# identity-disk-clock.net
KiCad netlist of a schematic drawn in EAGLE
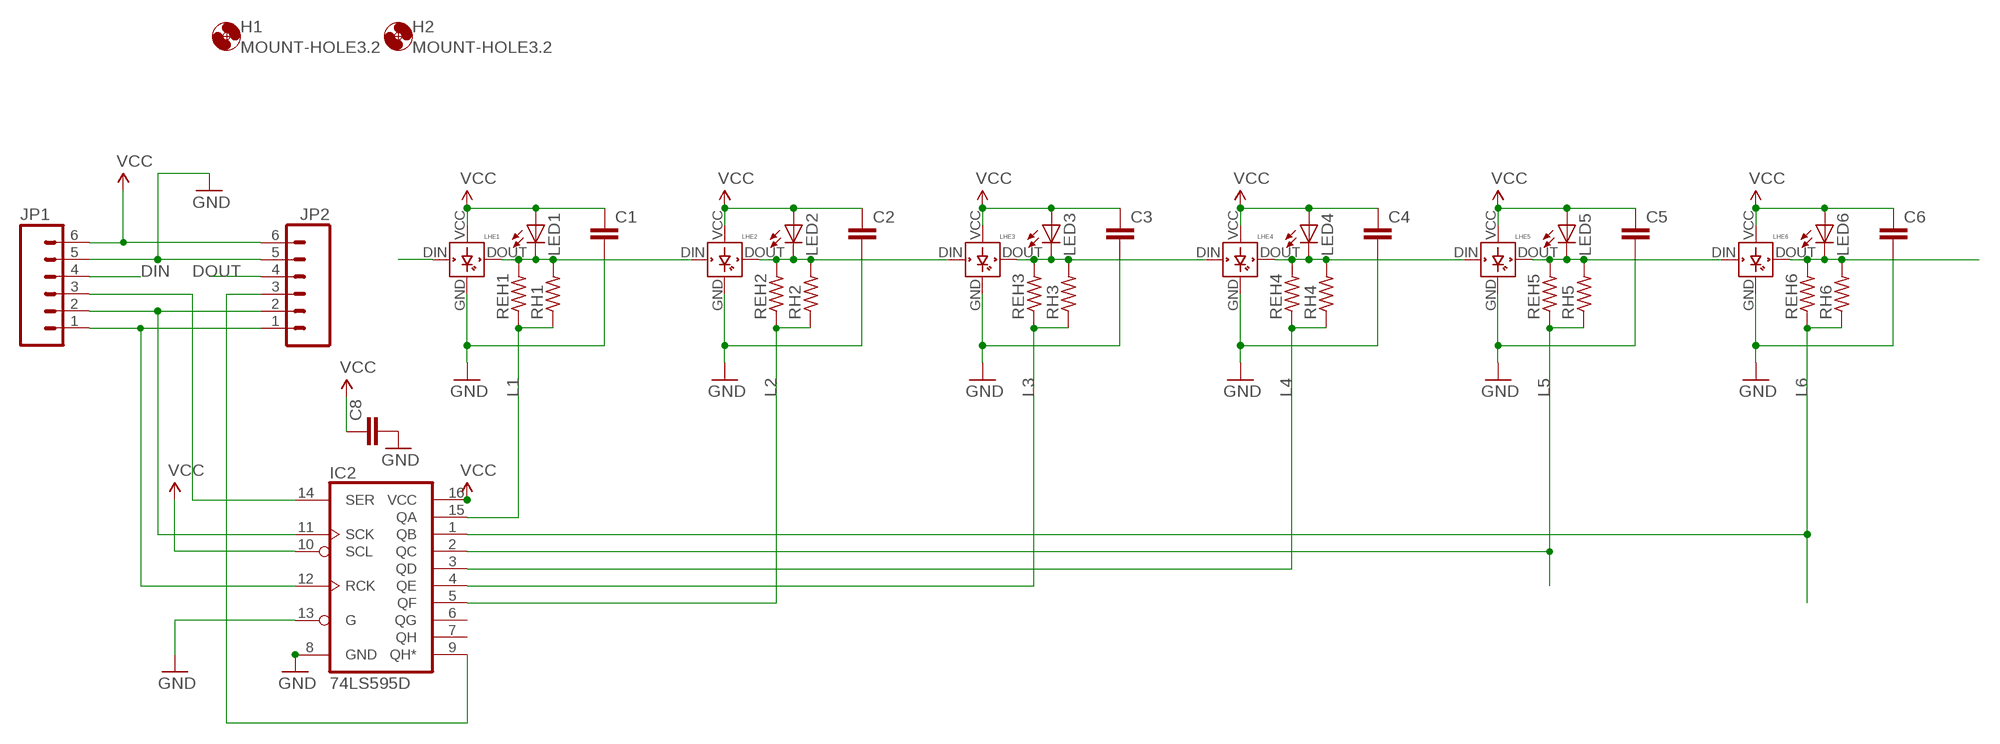
[diagram p0: schematic, sheet 1]

(export (version "E")
  (design (tool "Eeschema 10.0.6"))
  (components
    (comp (ref "C1")
      (value "C-EU050-024X044")
      (footprint "eagle-import:C050-024X044")
      (libsource (lib "eagle-import") (part "C-EU050-024X044"))
    )
    (comp (ref "C2")
      (value "C-EU050-024X044")
      (footprint "eagle-import:C050-024X044")
      (libsource (lib "eagle-import") (part "C-EU050-024X044"))
    )
    (comp (ref "C3")
      (value "C-EU050-024X044")
      (footprint "eagle-import:C050-024X044")
      (libsource (lib "eagle-import") (part "C-EU050-024X044"))
    )
    (comp (ref "C4")
      (value "C-EU050-024X044")
      (footprint "eagle-import:C050-024X044")
      (libsource (lib "eagle-import") (part "C-EU050-024X044"))
    )
    (comp (ref "C5")
      (value "C-EU050-024X044")
      (footprint "eagle-import:C050-024X044")
      (libsource (lib "eagle-import") (part "C-EU050-024X044"))
    )
    (comp (ref "C6")
      (value "C-EU050-024X044")
      (footprint "eagle-import:C050-024X044")
      (libsource (lib "eagle-import") (part "C-EU050-024X044"))
    )
    (comp (ref "C8")
      (value "C-EUC0402")
      (footprint "eagle-import:C0402")
      (libsource (lib "eagle-import") (part "resistor_C-EUC0402"))
    )
    (comp (ref "H1")
      (value "MOUNT-HOLE3.2")
      (footprint "eagle-import:3,2")
      (libsource (lib "eagle-import") (part "MOUNT-HOLE3.2"))
    )
    (comp (ref "H2")
      (value "MOUNT-HOLE3.2")
      (footprint "eagle-import:3,2")
      (libsource (lib "eagle-import") (part "MOUNT-HOLE3.2"))
    )
    (comp (ref "IC2")
      (value "74LS595D")
      (footprint "eagle-import:SO16")
      (libsource (lib "eagle-import") (part "74595DLS"))
    )
    (comp (ref "JP1")
      (value "M06LOCK")
      (footprint "eagle-import:1X06_LOCK")
      (libsource (lib "eagle-import") (part "M06LOCK"))
    )
    (comp (ref "JP2")
      (value "M06LOCK")
      (footprint "eagle-import:1X06_LOCK")
      (libsource (lib "eagle-import") (part "M06LOCK"))
    )
    (comp (ref "LED1")
      (value "LEDMICRO-SIDELED")
      (footprint "eagle-import:MICRO-SIDELED")
      (libsource (lib "eagle-import") (part "LEDMICRO-SIDELED"))
    )
    (comp (ref "LED2")
      (value "LEDMICRO-SIDELED")
      (footprint "eagle-import:MICRO-SIDELED")
      (libsource (lib "eagle-import") (part "LEDMICRO-SIDELED"))
    )
    (comp (ref "LED3")
      (value "LEDMICRO-SIDELED")
      (footprint "eagle-import:MICRO-SIDELED")
      (libsource (lib "eagle-import") (part "LEDMICRO-SIDELED"))
    )
    (comp (ref "LED4")
      (value "LEDMICRO-SIDELED")
      (footprint "eagle-import:MICRO-SIDELED")
      (libsource (lib "eagle-import") (part "LEDMICRO-SIDELED"))
    )
    (comp (ref "LED5")
      (value "LEDMICRO-SIDELED")
      (footprint "eagle-import:MICRO-SIDELED")
      (libsource (lib "eagle-import") (part "LEDMICRO-SIDELED"))
    )
    (comp (ref "LED6")
      (value "LEDMICRO-SIDELED")
      (footprint "eagle-import:MICRO-SIDELED")
      (libsource (lib "eagle-import") (part "LEDMICRO-SIDELED"))
    )
    (comp (ref "LHE1")
      (value "WS2812B")
      (footprint "eagle-import:LED5MMRGBNP")
      (libsource (lib "eagle-import") (part "WS2812B"))
    )
    (comp (ref "LHE2")
      (value "WS2812B")
      (footprint "eagle-import:LED5MMRGBNP")
      (libsource (lib "eagle-import") (part "WS2812B"))
    )
    (comp (ref "LHE3")
      (value "WS2812B")
      (footprint "eagle-import:LED5MMRGBNP")
      (libsource (lib "eagle-import") (part "WS2812B"))
    )
    (comp (ref "LHE4")
      (value "WS2812B")
      (footprint "eagle-import:LED5MMRGBNP")
      (libsource (lib "eagle-import") (part "WS2812B"))
    )
    (comp (ref "LHE5")
      (value "WS2812B")
      (footprint "eagle-import:LED5MMRGBNP")
      (libsource (lib "eagle-import") (part "WS2812B"))
    )
    (comp (ref "LHE6")
      (value "WS2812B")
      (footprint "eagle-import:LED5MMRGBNP")
      (libsource (lib "eagle-import") (part "WS2812B"))
    )
    (comp (ref "REH1")
      (value "R-US_R0402")
      (footprint "eagle-import:R0402")
      (libsource (lib "eagle-import") (part "R-US_R0402"))
    )
    (comp (ref "REH2")
      (value "R-US_R0402")
      (footprint "eagle-import:R0402")
      (libsource (lib "eagle-import") (part "R-US_R0402"))
    )
    (comp (ref "REH3")
      (value "R-US_R0402")
      (footprint "eagle-import:R0402")
      (libsource (lib "eagle-import") (part "R-US_R0402"))
    )
    (comp (ref "REH4")
      (value "R-US_R0402")
      (footprint "eagle-import:R0402")
      (libsource (lib "eagle-import") (part "R-US_R0402"))
    )
    (comp (ref "REH5")
      (value "R-US_R0402")
      (footprint "eagle-import:R0402")
      (libsource (lib "eagle-import") (part "R-US_R0402"))
    )
    (comp (ref "REH6")
      (value "R-US_R0402")
      (footprint "eagle-import:R0402")
      (libsource (lib "eagle-import") (part "R-US_R0402"))
    )
    (comp (ref "RH1")
      (value "R-US_0204/5")
      (footprint "eagle-import:0204_5")
      (libsource (lib "eagle-import") (part "R-US_0204/5"))
    )
    (comp (ref "RH2")
      (value "R-US_0204/5")
      (footprint "eagle-import:0204_5")
      (libsource (lib "eagle-import") (part "R-US_0204/5"))
    )
    (comp (ref "RH3")
      (value "R-US_0204/5")
      (footprint "eagle-import:0204_5")
      (libsource (lib "eagle-import") (part "R-US_0204/5"))
    )
    (comp (ref "RH4")
      (value "R-US_0204/5")
      (footprint "eagle-import:0204_5")
      (libsource (lib "eagle-import") (part "R-US_0204/5"))
    )
    (comp (ref "RH5")
      (value "R-US_0204/5")
      (footprint "eagle-import:0204_5")
      (libsource (lib "eagle-import") (part "R-US_0204/5"))
    )
    (comp (ref "RH6")
      (value "R-US_0204/5")
      (footprint "eagle-import:0204_5")
      (libsource (lib "eagle-import") (part "R-US_0204/5"))
    )
  )
  (nets
    (net (code "1") (name "/DIN") (class "Default")
      (node (ref "JP1") (pin "4") (pinfunction "4_4") (pintype "passive"))
      (node (ref "LHE1") (pin "DIN") (pinfunction "DIN_DIN") (pintype "input"))
    )
    (net (code "2") (name "/DOUT") (class "Default")
      (node (ref "JP2") (pin "4") (pinfunction "4_4") (pintype "passive"))
      (node (ref "LED6") (pin "C") (pinfunction "C_C") (pintype "passive"))
      (node (ref "LHE6") (pin "DOUT") (pinfunction "DOUT_DOUT") (pintype "output"))
      (node (ref "REH6") (pin "2") (pinfunction "2_2") (pintype "passive"))
      (node (ref "RH6") (pin "2") (pinfunction "2_2") (pintype "passive"))
    )
    (net (code "3") (name "/L1") (class "Default")
      (node (ref "IC2") (pin "15") (pinfunction "QA_15") (pintype "tri_state"))
      (node (ref "REH1") (pin "1") (pinfunction "1_1") (pintype "passive"))
      (node (ref "RH1") (pin "1") (pinfunction "1_1") (pintype "passive"))
    )
    (net (code "4") (name "/L2") (class "Default")
      (node (ref "IC2") (pin "5") (pinfunction "QF_5") (pintype "tri_state"))
      (node (ref "REH2") (pin "1") (pinfunction "1_1") (pintype "passive"))
      (node (ref "RH2") (pin "1") (pinfunction "1_1") (pintype "passive"))
    )
    (net (code "5") (name "/L3") (class "Default")
      (node (ref "IC2") (pin "4") (pinfunction "QE_4") (pintype "tri_state"))
      (node (ref "REH3") (pin "1") (pinfunction "1_1") (pintype "passive"))
      (node (ref "RH3") (pin "1") (pinfunction "1_1") (pintype "passive"))
    )
    (net (code "6") (name "/L4") (class "Default")
      (node (ref "IC2") (pin "3") (pinfunction "QD_3") (pintype "tri_state"))
      (node (ref "REH4") (pin "1") (pinfunction "1_1") (pintype "passive"))
      (node (ref "RH4") (pin "1") (pinfunction "1_1") (pintype "passive"))
    )
    (net (code "7") (name "/L5") (class "Default")
      (node (ref "IC2") (pin "2") (pinfunction "QC_2") (pintype "tri_state"))
      (node (ref "REH5") (pin "1") (pinfunction "1_1") (pintype "passive"))
      (node (ref "RH5") (pin "1") (pinfunction "1_1") (pintype "passive"))
    )
    (net (code "8") (name "/L6") (class "Default")
      (node (ref "IC2") (pin "1") (pinfunction "QB_1") (pintype "tri_state"))
      (node (ref "REH6") (pin "1") (pinfunction "1_1") (pintype "passive"))
      (node (ref "RH6") (pin "1") (pinfunction "1_1") (pintype "passive"))
    )
    (net (code "9") (name "GND") (class "Default")
      (node (ref "C1") (pin "2") (pinfunction "2_2") (pintype "passive"))
      (node (ref "C2") (pin "2") (pinfunction "2_2") (pintype "passive"))
      (node (ref "C3") (pin "2") (pinfunction "2_2") (pintype "passive"))
      (node (ref "C4") (pin "2") (pinfunction "2_2") (pintype "passive"))
      (node (ref "C5") (pin "2") (pinfunction "2_2") (pintype "passive"))
      (node (ref "C6") (pin "2") (pinfunction "2_2") (pintype "passive"))
      (node (ref "C8") (pin "2") (pinfunction "2_2") (pintype "passive"))
      (node (ref "IC2") (pin "13") (pinfunction "G_13") (pintype "input"))
      (node (ref "IC2") (pin "8") (pinfunction "GND_8") (pintype "power_in"))
      (node (ref "JP1") (pin "5") (pinfunction "5_5") (pintype "passive"))
      (node (ref "JP2") (pin "5") (pinfunction "5_5") (pintype "passive"))
      (node (ref "LHE1") (pin "GND") (pinfunction "GND_GND") (pintype "bidirectional"))
      (node (ref "LHE2") (pin "GND") (pinfunction "GND_GND") (pintype "bidirectional"))
      (node (ref "LHE3") (pin "GND") (pinfunction "GND_GND") (pintype "bidirectional"))
      (node (ref "LHE4") (pin "GND") (pinfunction "GND_GND") (pintype "bidirectional"))
      (node (ref "LHE5") (pin "GND") (pinfunction "GND_GND") (pintype "bidirectional"))
      (node (ref "LHE6") (pin "GND") (pinfunction "GND_GND") (pintype "bidirectional"))
    )
    (net (code "10") (name "Net-(IC2-QH*)") (class "Default")
      (node (ref "IC2") (pin "9") (pinfunction "QH*_9") (pintype "tri_state"))
      (node (ref "JP2") (pin "3") (pinfunction "3_3") (pintype "passive"))
    )
    (net (code "11") (name "Net-(IC2-RCK)") (class "Default")
      (node (ref "IC2") (pin "12") (pinfunction "RCK_12") (pintype "input"))
      (node (ref "JP1") (pin "1") (pinfunction "1_1") (pintype "passive"))
      (node (ref "JP2") (pin "1") (pinfunction "1_1") (pintype "passive"))
    )
    (net (code "12") (name "Net-(IC2-SCK)") (class "Default")
      (node (ref "IC2") (pin "11") (pinfunction "SCK_11") (pintype "input"))
      (node (ref "JP1") (pin "2") (pinfunction "2_2") (pintype "passive"))
      (node (ref "JP2") (pin "2") (pinfunction "2_2") (pintype "passive"))
    )
    (net (code "13") (name "Net-(IC2-SER)") (class "Default")
      (node (ref "IC2") (pin "14") (pinfunction "SER_14") (pintype "input"))
      (node (ref "JP1") (pin "3") (pinfunction "3_3") (pintype "passive"))
    )
    (net (code "14") (name "Net-(LED1-PadC)") (class "Default")
      (node (ref "LED1") (pin "C") (pinfunction "C_C") (pintype "passive"))
      (node (ref "LHE1") (pin "DOUT") (pinfunction "DOUT_DOUT") (pintype "output"))
      (node (ref "LHE2") (pin "DIN") (pinfunction "DIN_DIN") (pintype "input"))
      (node (ref "REH1") (pin "2") (pinfunction "2_2") (pintype "passive"))
      (node (ref "RH1") (pin "2") (pinfunction "2_2") (pintype "passive"))
    )
    (net (code "15") (name "Net-(LED2-PadC)") (class "Default")
      (node (ref "LED2") (pin "C") (pinfunction "C_C") (pintype "passive"))
      (node (ref "LHE2") (pin "DOUT") (pinfunction "DOUT_DOUT") (pintype "output"))
      (node (ref "LHE3") (pin "DIN") (pinfunction "DIN_DIN") (pintype "input"))
      (node (ref "REH2") (pin "2") (pinfunction "2_2") (pintype "passive"))
      (node (ref "RH2") (pin "2") (pinfunction "2_2") (pintype "passive"))
    )
    (net (code "16") (name "Net-(LED3-PadC)") (class "Default")
      (node (ref "LED3") (pin "C") (pinfunction "C_C") (pintype "passive"))
      (node (ref "LHE3") (pin "DOUT") (pinfunction "DOUT_DOUT") (pintype "output"))
      (node (ref "LHE4") (pin "DIN") (pinfunction "DIN_DIN") (pintype "input"))
      (node (ref "REH3") (pin "2") (pinfunction "2_2") (pintype "passive"))
      (node (ref "RH3") (pin "2") (pinfunction "2_2") (pintype "passive"))
    )
    (net (code "17") (name "Net-(LED4-PadC)") (class "Default")
      (node (ref "LED4") (pin "C") (pinfunction "C_C") (pintype "passive"))
      (node (ref "LHE4") (pin "DOUT") (pinfunction "DOUT_DOUT") (pintype "output"))
      (node (ref "LHE5") (pin "DIN") (pinfunction "DIN_DIN") (pintype "input"))
      (node (ref "REH4") (pin "2") (pinfunction "2_2") (pintype "passive"))
      (node (ref "RH4") (pin "2") (pinfunction "2_2") (pintype "passive"))
    )
    (net (code "18") (name "Net-(LED5-PadC)") (class "Default")
      (node (ref "LED5") (pin "C") (pinfunction "C_C") (pintype "passive"))
      (node (ref "LHE5") (pin "DOUT") (pinfunction "DOUT_DOUT") (pintype "output"))
      (node (ref "LHE6") (pin "DIN") (pinfunction "DIN_DIN") (pintype "input"))
      (node (ref "REH5") (pin "2") (pinfunction "2_2") (pintype "passive"))
      (node (ref "RH5") (pin "2") (pinfunction "2_2") (pintype "passive"))
    )
    (net (code "19") (name "VCC") (class "Default")
      (node (ref "C1") (pin "1") (pinfunction "1_1") (pintype "passive"))
      (node (ref "C2") (pin "1") (pinfunction "1_1") (pintype "passive"))
      (node (ref "C3") (pin "1") (pinfunction "1_1") (pintype "passive"))
      (node (ref "C4") (pin "1") (pinfunction "1_1") (pintype "passive"))
      (node (ref "C5") (pin "1") (pinfunction "1_1") (pintype "passive"))
      (node (ref "C6") (pin "1") (pinfunction "1_1") (pintype "passive"))
      (node (ref "C8") (pin "1") (pinfunction "1_1") (pintype "passive"))
      (node (ref "IC2") (pin "10") (pinfunction "SCL_10") (pintype "input"))
      (node (ref "IC2") (pin "16") (pinfunction "VCC_16") (pintype "power_in"))
      (node (ref "JP1") (pin "6") (pinfunction "6_6") (pintype "passive"))
      (node (ref "JP2") (pin "6") (pinfunction "6_6") (pintype "passive"))
      (node (ref "LED1") (pin "A") (pinfunction "A_A") (pintype "passive"))
      (node (ref "LED2") (pin "A") (pinfunction "A_A") (pintype "passive"))
      (node (ref "LED3") (pin "A") (pinfunction "A_A") (pintype "passive"))
      (node (ref "LED4") (pin "A") (pinfunction "A_A") (pintype "passive"))
      (node (ref "LED5") (pin "A") (pinfunction "A_A") (pintype "passive"))
      (node (ref "LED6") (pin "A") (pinfunction "A_A") (pintype "passive"))
      (node (ref "LHE1") (pin "VCC") (pinfunction "VDD_VCC") (pintype "bidirectional"))
      (node (ref "LHE2") (pin "VCC") (pinfunction "VDD_VCC") (pintype "bidirectional"))
      (node (ref "LHE3") (pin "VCC") (pinfunction "VDD_VCC") (pintype "bidirectional"))
      (node (ref "LHE4") (pin "VCC") (pinfunction "VDD_VCC") (pintype "bidirectional"))
      (node (ref "LHE5") (pin "VCC") (pinfunction "VDD_VCC") (pintype "bidirectional"))
      (node (ref "LHE6") (pin "VCC") (pinfunction "VDD_VCC") (pintype "bidirectional"))
    )
    (net (code "20") (name "unconnected-(IC2-QG-Pad6)") (class "Default")
      (node (ref "IC2") (pin "6") (pinfunction "QG_6") (pintype "tri_state"))
    )
    (net (code "21") (name "unconnected-(IC2-QH-Pad7)") (class "Default")
      (node (ref "IC2") (pin "7") (pinfunction "QH_7") (pintype "tri_state"))
    )
  )
)
